# Qwiic_Differential_Pressure_Sensor-SDP31.net
KiCad netlist of a schematic drawn in EAGLE
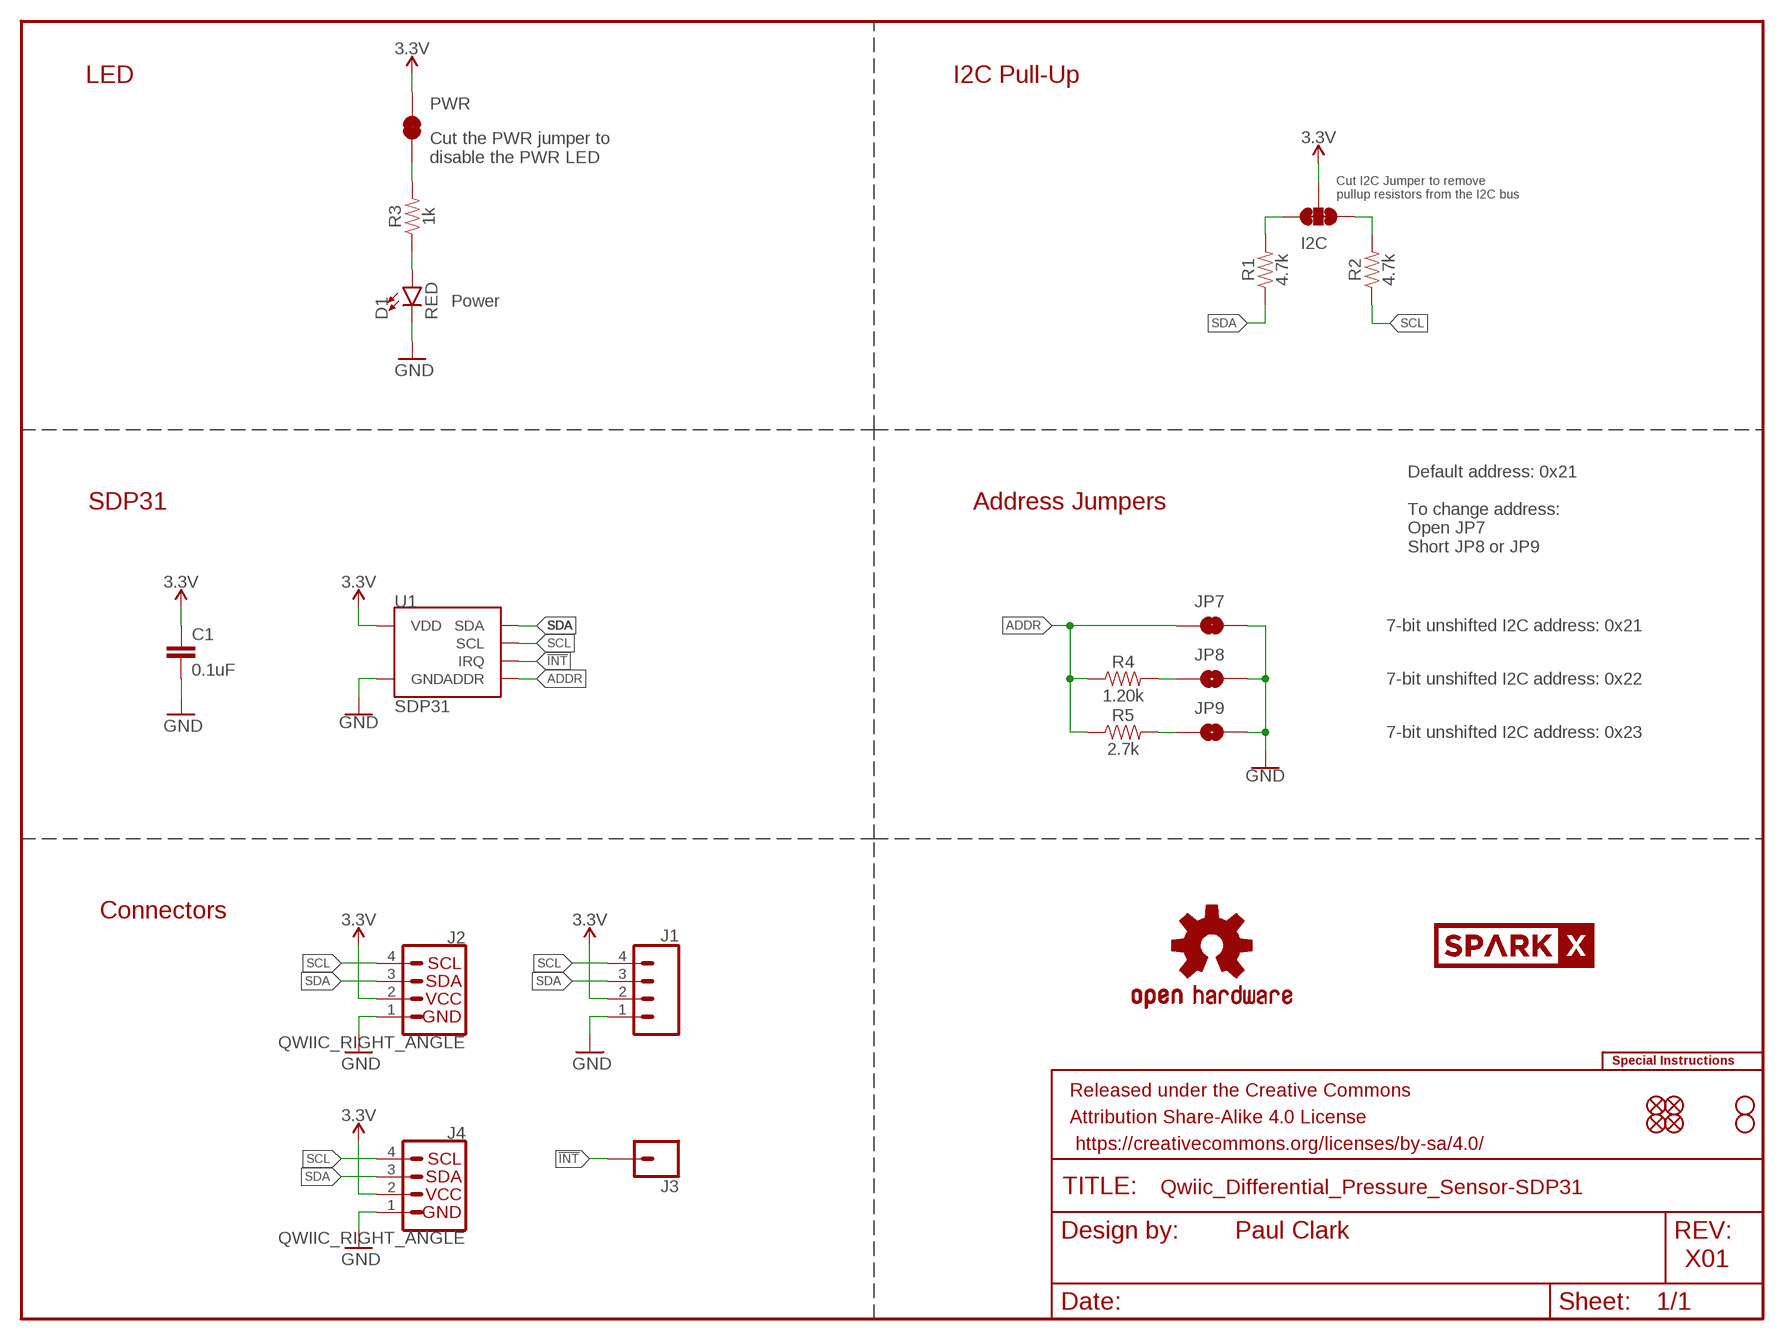
[diagram p0: schematic, sheet 1]

(export (version "E")
  (design (tool "Eeschema 10.0.6"))
  (components
    (comp (ref "C1")
      (value "0.1uF")
      (footprint "eagle-import:0603")
      (libsource (lib "eagle-import") (part "0.1UF-0603-25V-(+80/-20%)"))
    )
    (comp (ref "D1")
      (value "RED")
      (footprint "eagle-import:LED-0603")
      (libsource (lib "eagle-import") (part "LED-RED0603"))
    )
    (comp (ref "FRAME1")
      (value "FRAME-LETTER")
      (footprint "eagle-import:CREATIVE_COMMONS")
      (libsource (lib "eagle-import") (part "FRAME-LETTER"))
    )
    (comp (ref "I2C")
      (value "JUMPER-SMT_3_2-NC_TRACE_SILK")
      (footprint "eagle-import:SMT-JUMPER_3_2-NC_TRACE_SILK")
      (libsource (lib "eagle-import") (part "JUMPER-SMT_3_2-NC_TRACE_SILK"))
    )
    (comp (ref "J1")
      (value "CONN_041X04_NO_SILK")
      (footprint "eagle-import:1X04_NO_SILK")
      (libsource (lib "eagle-import") (part "CONN_041X04_NO_SILK"))
    )
    (comp (ref "J2")
      (value "QWIIC_RIGHT_ANGLE")
      (footprint "eagle-import:JST04_1MM_RA")
      (libsource (lib "eagle-import") (part "QWIIC_CONNECTORJS-1MM"))
    )
    (comp (ref "J3")
      (value "CONN_01PTH_NO_SILK_YES_STOP")
      (footprint "eagle-import:1X01_NO_SILK")
      (libsource (lib "eagle-import") (part "CONN_01PTH_NO_SILK_YES_STOP"))
    )
    (comp (ref "J4")
      (value "QWIIC_RIGHT_ANGLE")
      (footprint "eagle-import:JST04_1MM_RA")
      (libsource (lib "eagle-import") (part "QWIIC_CONNECTORJS-1MM"))
    )
    (comp (ref "JP1")
      (value "FIDUCIALUFIDUCIAL")
      (footprint "eagle-import:FIDUCIAL-MICRO")
      (libsource (lib "eagle-import") (part "FIDUCIALUFIDUCIAL"))
    )
    (comp (ref "JP2")
      (value "FIDUCIALUFIDUCIAL")
      (footprint "eagle-import:FIDUCIAL-MICRO")
      (libsource (lib "eagle-import") (part "FIDUCIALUFIDUCIAL"))
    )
    (comp (ref "JP3")
      (value "STAND-OFF")
      (footprint "eagle-import:STAND-OFF")
      (libsource (lib "eagle-import") (part "STAND-OFF"))
    )
    (comp (ref "JP4")
      (value "STAND-OFF")
      (footprint "eagle-import:STAND-OFF")
      (libsource (lib "eagle-import") (part "STAND-OFF"))
    )
    (comp (ref "JP5")
      (value "FIDUCIALUFIDUCIAL")
      (footprint "eagle-import:FIDUCIAL-MICRO")
      (libsource (lib "eagle-import") (part "FIDUCIALUFIDUCIAL"))
    )
    (comp (ref "JP6")
      (value "FIDUCIALUFIDUCIAL")
      (footprint "eagle-import:FIDUCIAL-MICRO")
      (libsource (lib "eagle-import") (part "FIDUCIALUFIDUCIAL"))
    )
    (comp (ref "JP7")
      (value "JUMPER-SMT_2_NC_TRACE_SILK")
      (footprint "eagle-import:SMT-JUMPER_2_NC_TRACE_SILK")
      (libsource (lib "eagle-import") (part "JUMPER-SMT_2_NC_TRACE_SILK"))
    )
    (comp (ref "JP8")
      (value "JUMPER-SMT_2_NO_SILK")
      (footprint "eagle-import:SMT-JUMPER_2_NO_SILK")
      (libsource (lib "eagle-import") (part "JUMPER-SMT_2_NO_SILK"))
    )
    (comp (ref "JP9")
      (value "JUMPER-SMT_2_NO_SILK")
      (footprint "eagle-import:SMT-JUMPER_2_NO_SILK")
      (libsource (lib "eagle-import") (part "JUMPER-SMT_2_NO_SILK"))
    )
    (comp (ref "LOGO1")
      (value "SPECIAL_INSTRUCTIONS-ORDERING")
      (footprint "eagle-import:ORDERING_INSTRUCTIONS")
      (libsource (lib "eagle-import") (part "SPECIAL_INSTRUCTIONS-ORDERING"))
    )
    (comp (ref "LOGO5")
      (value "OSHW-LOGOS")
      (footprint "eagle-import:OSHW-LOGO-S")
      (libsource (lib "eagle-import") (part "OSHW-LOGOS"))
    )
    (comp (ref "PWR")
      (value "JUMPER-SMT_2_NC_TRACE_SILK")
      (footprint "eagle-import:SMT-JUMPER_2_NC_TRACE_SILK")
      (libsource (lib "eagle-import") (part "JUMPER-SMT_2_NC_TRACE_SILK"))
    )
    (comp (ref "R1")
      (value "4.7k")
      (footprint "eagle-import:0603")
      (libsource (lib "eagle-import") (part "4.7KOHM-0603-1/10W-1%"))
    )
    (comp (ref "R2")
      (value "4.7k")
      (footprint "eagle-import:0603")
      (libsource (lib "eagle-import") (part "4.7KOHM-0603-1/10W-1%"))
    )
    (comp (ref "R3")
      (value "1k")
      (footprint "eagle-import:0603")
      (libsource (lib "eagle-import") (part "1KOHM-0603-1/10W-1%"))
    )
    (comp (ref "R4")
      (value "1.20k")
      (footprint "eagle-import:0603")
      (libsource (lib "eagle-import") (part "1.20KOHM-0603-1/10W-1%"))
    )
    (comp (ref "R5")
      (value "2.7k")
      (footprint "eagle-import:0603")
      (libsource (lib "eagle-import") (part "2.7KOHM-0603-1/10W-1%"))
    )
    (comp (ref "U$18")
      (value "SPARKX-LOGO3")
      (footprint "eagle-import:SPARKX-SMALL")
      (libsource (lib "eagle-import") (part "SPARKX-LOGO3"))
    )
    (comp (ref "U1")
      (value "SDP31")
      (footprint "eagle-import:SDP3X")
      (libsource (lib "eagle-import") (part "SDP3X_SDP31"))
    )
  )
  (nets
    (net (code "1") (name "/~{INT}") (class "Default")
      (node (ref "J3") (pin "1") (pinfunction "1_1") (pintype "passive"))
      (node (ref "U1") (pin "4") (pinfunction "IRQ_4") (pintype "output"))
    )
    (net (code "2") (name "3.3V") (class "Default")
      (node (ref "C1") (pin "1") (pinfunction "1_1") (pintype "passive"))
      (node (ref "I2C") (pin "2") (pinfunction "2_2") (pintype "passive"))
      (node (ref "J1") (pin "2") (pinfunction "2_2") (pintype "passive"))
      (node (ref "J2") (pin "2") (pinfunction "2_2") (pintype "power_in"))
      (node (ref "J4") (pin "2") (pinfunction "2_2") (pintype "power_in"))
      (node (ref "PWR") (pin "2") (pinfunction "2_2") (pintype "passive"))
      (node (ref "U1") (pin "7") (pinfunction "VDD_7") (pintype "power_in"))
    )
    (net (code "3") (name "ADDR") (class "Default")
      (node (ref "JP7") (pin "1") (pinfunction "1_1") (pintype "passive"))
      (node (ref "R4") (pin "1") (pinfunction "1_1") (pintype "passive"))
      (node (ref "R5") (pin "1") (pinfunction "1_1") (pintype "passive"))
      (node (ref "U1") (pin "9") (pinfunction "ADDR_9") (pintype "bidirectional"))
    )
    (net (code "4") (name "GND") (class "Default")
      (node (ref "C1") (pin "2") (pinfunction "2_2") (pintype "passive"))
      (node (ref "D1") (pin "C") (pinfunction "C_C") (pintype "passive"))
      (node (ref "J1") (pin "1") (pinfunction "1_1") (pintype "passive"))
      (node (ref "J2") (pin "1") (pinfunction "1_1") (pintype "power_in"))
      (node (ref "J4") (pin "1") (pinfunction "1_1") (pintype "power_in"))
      (node (ref "JP7") (pin "2") (pinfunction "2_2") (pintype "passive"))
      (node (ref "JP8") (pin "2") (pinfunction "2_2") (pintype "passive"))
      (node (ref "JP9") (pin "2") (pinfunction "2_2") (pintype "passive"))
      (node (ref "U1") (pin "1") (pinfunction "GND_1") (pintype "power_in"))
      (node (ref "U1") (pin "10") (pinfunction "GND_10") (pintype "power_in"))
      (node (ref "U1") (pin "11") (pinfunction "GND_11") (pintype "power_in"))
      (node (ref "U1") (pin "2") (pinfunction "GND_2") (pintype "power_in"))
      (node (ref "U1") (pin "3") (pinfunction "GND_3") (pintype "power_in"))
      (node (ref "U1") (pin "6") (pinfunction "GND_6") (pintype "power_in"))
      (node (ref "U1") (pin "DIEPAD1") (pinfunction "GND_DIEPAD1") (pintype "power_in"))
      (node (ref "U1") (pin "DIEPAD2") (pinfunction "GND_DIEPAD2") (pintype "power_in"))
    )
    (net (code "5") (name "Net-(D1-PadA)") (class "Default")
      (node (ref "D1") (pin "A") (pinfunction "A_A") (pintype "passive"))
      (node (ref "R3") (pin "1") (pinfunction "1_1") (pintype "passive"))
    )
    (net (code "6") (name "Net-(I2C-Pad1)") (class "Default")
      (node (ref "I2C") (pin "1") (pinfunction "1_1") (pintype "passive"))
      (node (ref "R2") (pin "2") (pinfunction "2_2") (pintype "passive"))
    )
    (net (code "7") (name "Net-(I2C-Pad3)") (class "Default")
      (node (ref "I2C") (pin "3") (pinfunction "3_3") (pintype "passive"))
      (node (ref "R1") (pin "2") (pinfunction "2_2") (pintype "passive"))
    )
    (net (code "8") (name "Net-(JP8-Pad1)") (class "Default")
      (node (ref "JP8") (pin "1") (pinfunction "1_1") (pintype "passive"))
      (node (ref "R4") (pin "2") (pinfunction "2_2") (pintype "passive"))
    )
    (net (code "9") (name "Net-(JP9-Pad1)") (class "Default")
      (node (ref "JP9") (pin "1") (pinfunction "1_1") (pintype "passive"))
      (node (ref "R5") (pin "2") (pinfunction "2_2") (pintype "passive"))
    )
    (net (code "10") (name "Net-(PWR-Pad1)") (class "Default")
      (node (ref "PWR") (pin "1") (pinfunction "1_1") (pintype "passive"))
      (node (ref "R3") (pin "2") (pinfunction "2_2") (pintype "passive"))
    )
    (net (code "11") (name "SCL") (class "Default")
      (node (ref "J1") (pin "4") (pinfunction "4_4") (pintype "passive"))
      (node (ref "J2") (pin "4") (pinfunction "4_4") (pintype "passive"))
      (node (ref "J4") (pin "4") (pinfunction "4_4") (pintype "passive"))
      (node (ref "R2") (pin "1") (pinfunction "1_1") (pintype "passive"))
      (node (ref "U1") (pin "5") (pinfunction "SCL_5") (pintype "bidirectional"))
    )
    (net (code "12") (name "SDA") (class "Default")
      (node (ref "J1") (pin "3") (pinfunction "3_3") (pintype "passive"))
      (node (ref "J2") (pin "3") (pinfunction "3_3") (pintype "passive"))
      (node (ref "J4") (pin "3") (pinfunction "3_3") (pintype "passive"))
      (node (ref "R1") (pin "1") (pinfunction "1_1") (pintype "passive"))
      (node (ref "U1") (pin "8") (pinfunction "SDA_8") (pintype "bidirectional"))
    )
  )
)
